# FLYBACK_220-24V.net
KiCad netlist of a schematic drawn in Altium Designer
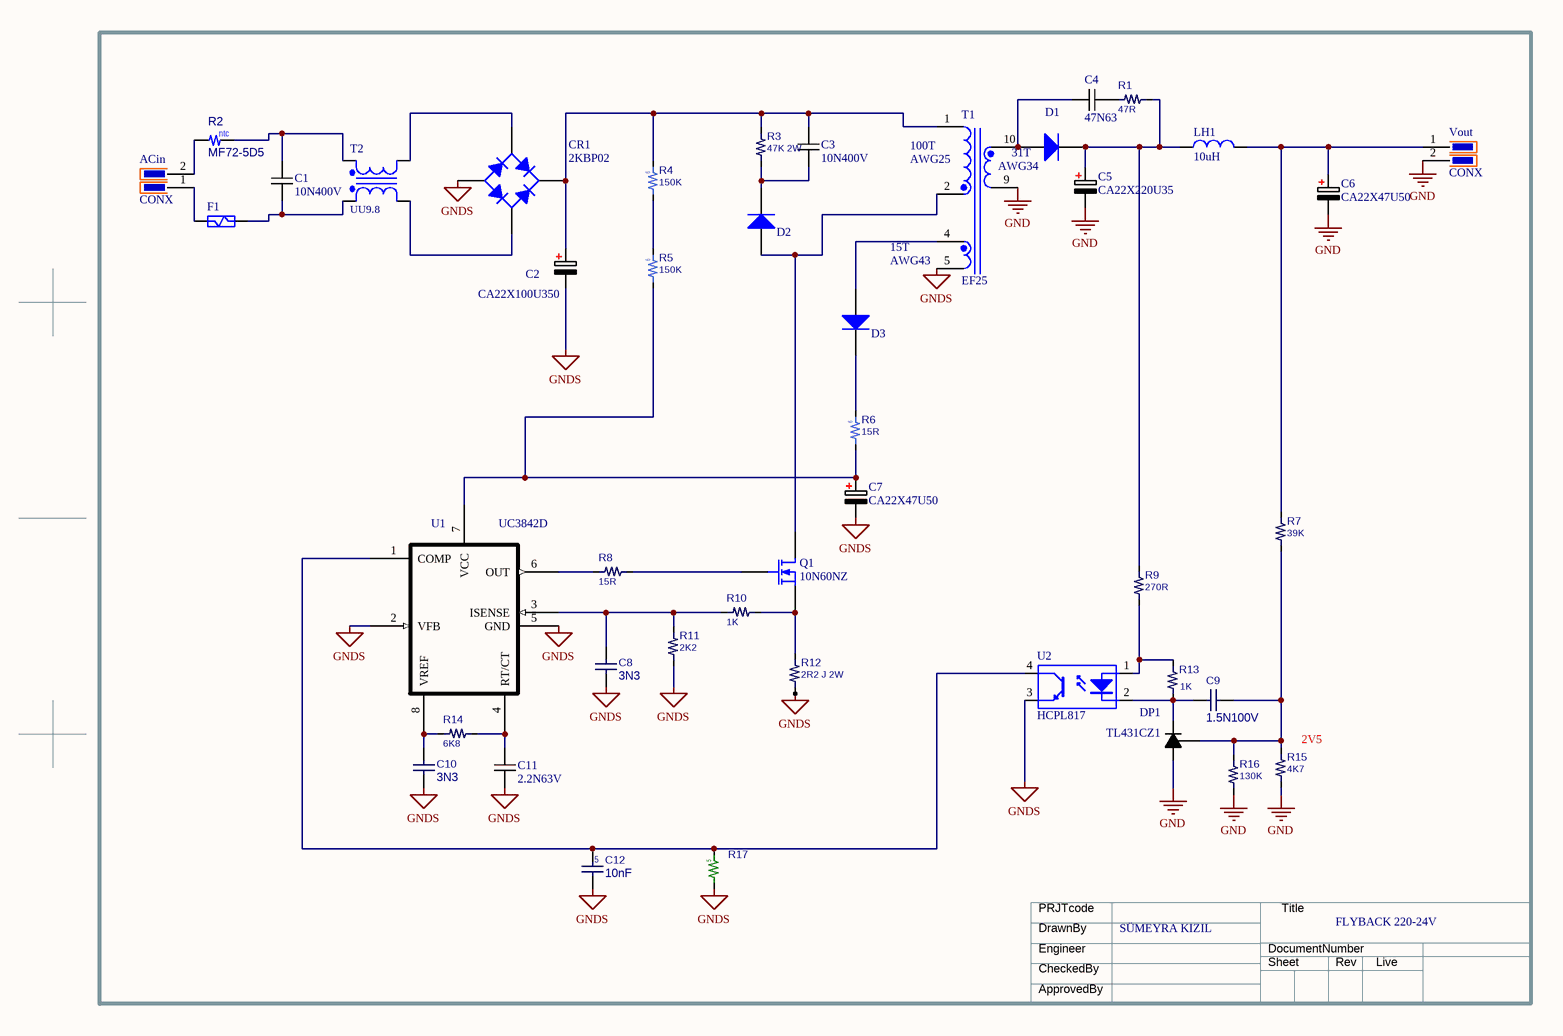
[diagram p0: FLYBACK 220-24V.SchDoc]

(export (version "E")
  (design (tool "Eeschema 10.0.6"))
  (components
    (comp (ref "ACin")
      (value "CONX")
      (footprint "MBDK122")
      (description "X PIN CONN")
      (libsource (lib "") (part "CON2X_1"))
    )
    (comp (ref "C1")
      (value "10N400V")
      (footprint "RAD0.3")
      (description "METALLISED POLYSTER CAP")
      (fields
        (field (name "MANUFACTURER") "Generic Components")
        (field (name "Comment") "CM03Y10N0V400")
        (field (name "PUBLISHER") "NET")
      )
      (libsource (lib "CM") (part "CM03Y10N0V400"))
    )
    (comp (ref "C2")
      (value "CA22X100U350")
      (footprint "24X30")
      (description "Electrolytic Capacitor general use")
      (fields (field (name "MANUFACTURER") "Generic Components"))
      (libsource (lib "CA22") (part "CA22X68U350"))
    )
    (comp (ref "C3")
      (value "10N400V")
      (footprint "RAD0.2")
      (description "METALLISED POLYSTER CAP")
      (fields
        (field (name "MANUFACTURER") "Generic Components")
        (field (name "Comment") "CM02Y10N0V400")
        (field (name "PUBLISHER") "NET")
      )
      (libsource (lib "CM") (part "CM02Y10N0V400"))
    )
    (comp (ref "C4")
      (value "47N63")
      (footprint "RAD0.2")
      (description "METALLISED POLYSTER CAP")
      (fields
        (field (name "MANUFACTURER") "Generic Components")
        (field (name "Comment") "CM02Y47N0V63")
        (field (name "PUBLISHER") "NET")
      )
      (libsource (lib "CM") (part "CM02Y47N0V63"))
    )
    (comp (ref "C5")
      (value "CA22X220U35")
      (footprint "8X12XP150")
      (description "Electrolytic Capacitor general use")
      (fields (field (name "MANUFACTURER") "Generic Components"))
      (libsource (lib "CA22") (part "CA22X220U35"))
    )
    (comp (ref "C6")
      (value "CA22X47U50")
      (footprint "8X12XP150")
      (description "Electrolytic Capacitor general use")
      (fields (field (name "MANUFACTURER") "Generic Components"))
      (libsource (lib "CA22") (part "CA22X47U50"))
    )
    (comp (ref "C7")
      (value "CA22X47U50")
      (footprint "6.3X11")
      (description "Electrolytic Capacitor general use")
      (fields (field (name "MANUFACTURER") "Generic Components"))
      (libsource (lib "CA22") (part "CA22X47U50"))
    )
    (comp (ref "C8")
      (value "3N3")
      (footprint "RAD0.2")
      (description "CERAMIC DISC CAPACITOR")
      (fields
        (field (name "MANUFACTURER") "Generic Components")
        (field (name "Comment") "CB02X3N30")
        (field (name "PUBLISHER") "Nettas Technology Center")
      )
      (libsource (lib "Sumeyra_1") (part "CB02X3N30"))
    )
    (comp (ref "C9")
      (value "1.5N100V")
      (footprint "RAD0.2")
      (description "CERAMIC DISC CAPACITOR")
      (fields
        (field (name "MANUFACTURER") "Generic Components")
        (field (name "Comment") "CB02X1N50")
        (field (name "PUBLISHER") "Nettas Technology Center")
      )
      (libsource (lib "CM") (part "CB02X1N50"))
    )
    (comp (ref "C10")
      (value "3N3")
      (footprint "RAD0.2")
      (description "CERAMIC DISC CAPACITOR")
      (fields
        (field (name "MANUFACTURER") "Generic Components")
        (field (name "Comment") "CB02X3N30")
        (field (name "PUBLISHER") "Nettas Technology Center")
      )
      (libsource (lib "Sumeyra_1") (part "CB02X3N30"))
    )
    (comp (ref "C11")
      (value "2.2N63V")
      (footprint "RAD0.2")
      (description "METALLISED POLYSTER CAP")
      (fields
        (field (name "MANUFACTURER") "Generic Components")
        (field (name "Comment") "CM02Y2N20V63")
        (field (name "PUBLISHER") "NET")
      )
      (libsource (lib "CM") (part "CM02Y2N20V63"))
    )
    (comp (ref "C12")
      (value "10nF")
      (footprint "RAD0.3")
      (description "TH Capacitor")
      (fields
        (field (name "MANUFACTURER") "Generic Components")
        (field (name "Comment") "CHC0805-10N0")
        (field (name "PUBLISHER") "Nettas Technology Center")
      )
      (libsource (lib "CHC") (part "CHC0805-10N0"))
    )
    (comp (ref "CR1")
      (value "2KBP02")
      (footprint "KBU")
      (description "2 Amp Single Phase Rectifier Bridge")
      (fields
        (field (name "MANUFACTURER") "International Rectifier")
        (field (name "PUBLISHER") "Altium Hobart Technology Centre")
      )
      (libsource (lib "Sumeyra_1") (part "2KBP02"))
    )
    (comp (ref "D1")
      (value "UF5402")
      (footprint "DO-41")
      (description "General Purpose ULTRA FAST Rectifiers")
      (fields
        (field (name "MANUFACTURER") "Generic Components")
        (field (name "PUBLISHER") "Altium Hobart Technology Centre")
      )
      (libsource (lib "DIODE") (part "UF5402"))
    )
    (comp (ref "D2")
      (value "UF4007")
      (footprint "DO-41")
      (description "General Purpose ULTRA FAST Rectifiers")
      (fields
        (field (name "MANUFACTURER") "Generic Components")
        (field (name "PUBLISHER") "Altium Hobart Technology Centre")
      )
      (libsource (lib "DIODE") (part "UF4007"))
    )
    (comp (ref "D3")
      (value "UF4007")
      (footprint "DO-41")
      (description "General Purpose ULTRA FAST Rectifiers")
      (fields
        (field (name "MANUFACTURER") "Generic Components")
        (field (name "PUBLISHER") "Altium Hobart Technology Centre")
      )
      (libsource (lib "DIODE") (part "UF4007"))
    )
    (comp (ref "DP1")
      (value "TL431CZ1")
      (footprint "TL431")
      (description "Programmable Voltage Reference")
      (fields
        (field (name "MANUFACTURER") "ST-Microelectronics")
        (field (name "PUBLISHER") "Altium Hobart Technology Centre")
      )
      (libsource (lib "INTEGRATED") (part "TL431CZ1"))
    )
    (comp (ref "F1")
      (value "~")
      (footprint "Sigorta Tutucu")
      (description "Fuse")
      (fields
        (field (name "MANUFACTURER") "Generic Components")
        (field (name "PUBLISHER") "Altium Hobart Technology Centre")
      )
      (libsource (lib "Sumeyra_1") (part "FUSE-GL600"))
    )
    (comp (ref "LH1")
      (value "10uH")
      (footprint "10X13L")
      (description "LH 10uH")
      (fields
        (field (name "MANUFACTURER") "Generic Components")
        (field (name "PUBLISHER") "Altium Hobart Technology Centre")
      )
      (libsource (lib "MAGNETIC") (part "Inductor"))
    )
    (comp (ref "Q1")
      (value "10N60NZ")
      (footprint "TO220")
      (description "FULLY AUTOPROTECTED POWER MOSFET")
      (fields
        (field (name "MANUFACTURER") "Generic Components")
        (field (name "PUBLISHER") "Altium Hobart Technology Centre")
      )
      (libsource (lib "Sumeyra_1") (part "10N60NZ"))
    )
    (comp (ref "R1")
      (value "47R")
      (footprint "AXIAL0.4")
      (description "AXIAL Resistor 0.4")
      (fields
        (field (name "MANUFACTURER") "Generic Components")
        (field (name "Comment") "RF24-47R0")
        (field (name "PUBLISHER") "Nettas Technology Center")
      )
      (libsource (lib "RF24") (part "RF24-47R0"))
    )
    (comp (ref "R2")
      (value "MF72-5D5")
      (footprint "RAD0.3NTC")
      (description "Power NTC Thermistor")
      (fields
        (field (name "MANUFACTURER") "Generic Components")
        (field (name "PUBLISHER") "Nettas Technology Center")
      )
      (libsource (lib "RF24") (part "MF72-5D5"))
    )
    (comp (ref "R3")
      (value "47K 2W")
      (footprint "AXIAL0.7")
      (description "AXIAL Resistor 0.7")
      (fields
        (field (name "MANUFACTURER") "Generic Components")
        (field (name "Comment") "RF13-47K0")
        (field (name "PUBLISHER") "Nettas Technology Center")
      )
      (libsource (lib "Sumeyra_1") (part "RF13-47K0"))
    )
    (comp (ref "R4")
      (value "150K")
      (footprint "AXIAL0.4")
      (description "SMD Resistor")
      (fields
        (field (name "MANUFACTURER") "Generic Components")
        (field (name "Comment") "CHR1206-15R0")
        (field (name "PUBLISHER") "Nettas Technology Center")
      )
      (libsource (lib "CHR") (part "CHR1206-15R0"))
    )
    (comp (ref "R5")
      (value "150K")
      (footprint "AXIAL0.4")
      (description "SMD Resistor")
      (fields
        (field (name "MANUFACTURER") "Generic Components")
        (field (name "Comment") "CHR1206-15R0")
        (field (name "PUBLISHER") "Nettas Technology Center")
      )
      (libsource (lib "CHR") (part "CHR1206-15R0"))
    )
    (comp (ref "R6")
      (value "15R")
      (footprint "AXIAL0.5")
      (description "SMD Resistor")
      (fields
        (field (name "MANUFACTURER") "Generic Components")
        (field (name "Comment") "CHR1206-15R0")
        (field (name "PUBLISHER") "Nettas Technology Center")
      )
      (libsource (lib "CHR") (part "CHR1206-15R0"))
    )
    (comp (ref "R7")
      (value "39K")
      (footprint "AXIAL0.5")
      (description "AXIAL Resistor")
      (fields
        (field (name "MANUFACTURER") "Generic Components")
        (field (name "Comment") "RF24-39K0")
        (field (name "PUBLISHER") "Nettas Technology Center")
      )
      (libsource (lib "RF24") (part "RF24-39K0"))
    )
    (comp (ref "R8")
      (value "15R")
      (footprint "AXIAL0.4")
      (description "AXIAL Resistor")
      (fields
        (field (name "MANUFACTURER") "Generic Components")
        (field (name "Comment") "RF24-15R0")
        (field (name "PUBLISHER") "Nettas Technology Center")
      )
      (libsource (lib "RF24") (part "RF24-15R0"))
    )
    (comp (ref "R9")
      (value "270R")
      (footprint "AXIAL0.6")
      (description "AXIAL Resistor")
      (fields
        (field (name "MANUFACTURER") "Generic Components")
        (field (name "Comment") "RF24-270R")
        (field (name "PUBLISHER") "Nettas Technology Center")
      )
      (libsource (lib "RF24") (part "RF24-270R"))
    )
    (comp (ref "R10")
      (value "1K")
      (footprint "AXIAL0.4")
      (description "AXIAL Resistor")
      (fields
        (field (name "MANUFACTURER") "Generic Components")
        (field (name "Comment") "RF24-1K00")
        (field (name "PUBLISHER") "Nettas Technology Center")
      )
      (libsource (lib "RF24") (part "RF24-1K00"))
    )
    (comp (ref "R11")
      (value "2K2")
      (footprint "AXIAL0.4")
      (description "AXIAL Resistor")
      (fields
        (field (name "MANUFACTURER") "Generic Components")
        (field (name "Comment") "RF24-2K20")
        (field (name "PUBLISHER") "Nettas Technology Center")
      )
      (libsource (lib "RF24") (part "RF24-2K20"))
    )
    (comp (ref "R12")
      (value "2R2 J 2W")
      (footprint "AXIAL0.7")
      (description "AXIAL WIRE Resistor")
      (fields
        (field (name "MANUFACTURER") "Generic Components")
        (field (name "Comment") "RW02J-2R20")
        (field (name "PUBLISHER") "Nettas Technology Center")
      )
      (libsource (lib "RF24") (part "RW02J-2R20"))
    )
    (comp (ref "R13")
      (value "1K")
      (footprint "AXIAL0.4")
      (description "AXIAL Resistor")
      (fields
        (field (name "MANUFACTURER") "Generic Components")
        (field (name "Comment") "RF24-1K00")
        (field (name "PUBLISHER") "Nettas Technology Center")
      )
      (libsource (lib "RF24") (part "RF24-1K00"))
    )
    (comp (ref "R14")
      (value "6K8")
      (footprint "AXIAL0.4")
      (description "AXIAL Resistor")
      (fields
        (field (name "MANUFACTURER") "Generic Components")
        (field (name "Comment") "RF24-6K80")
        (field (name "PUBLISHER") "Nettas Technology Center")
      )
      (libsource (lib "RF24") (part "RF24-6K80"))
    )
    (comp (ref "R15")
      (value "4K7")
      (footprint "AXIAL0.4")
      (description "AXIAL Resistor")
      (fields
        (field (name "MANUFACTURER") "Generic Components")
        (field (name "Comment") "RF24-4K70")
        (field (name "PUBLISHER") "Nettas Technology Center")
      )
      (libsource (lib "RF24") (part "RF24-4K70"))
    )
    (comp (ref "R16")
      (value "130K")
      (footprint "AXIAL0.4")
      (description "AXIAL Resistor")
      (fields
        (field (name "MANUFACTURER") "Generic Components")
        (field (name "Comment") "RF24-130K")
        (field (name "PUBLISHER") "Nettas Technology Center")
      )
      (libsource (lib "RF24") (part "RF24-130K"))
    )
    (comp (ref "R17")
      (value "CHR0805-10K0")
      (footprint "AXIAL0.4")
      (description "TH Resistor")
      (fields
        (field (name "MANUFACTURER") "Generic Components")
        (field (name "PUBLISHER") "Nettas Technology Center")
      )
      (libsource (lib "CHR") (part "CHR0805-10K0"))
    )
    (comp (ref "T1")
      (value "EF25")
      (footprint "TRF_EF25_40")
      (description "TRF_EF25_40")
      (fields
        (field (name "MANUFACTURER") "Generic Components")
        (field (name "PUBLISHER") "Altium Hobart Technology Centre")
      )
      (libsource (lib "Sumeyra_1") (part "TRF_EF25_40"))
    )
    (comp (ref "T2")
      (value "UU9.8")
      (footprint "LFILT11")
      (description "LINEFILTER CUPL TRF")
      (libsource (lib "Sumeyra_1") (part "LINEFILTER12"))
    )
    (comp (ref "U1")
      (value "UC3842D")
      (footprint "DIP8")
      (description "SMPS Controller")
      (libsource (lib "INTEGRATED") (part "UC3844D1"))
    )
    (comp (ref "U2")
      (value "HCPL817")
      (footprint "DIP4")
      (description "High Density Mounting Type Photocoupler")
      (fields (field (name "MANUFACTURER") "www.cosmo-ic.com"))
      (libsource (lib "OPTO") (part "HCPL817"))
    )
    (comp (ref "Vout")
      (value "CONX")
      (footprint "MBDK122")
      (description "X PIN CONN")
      (libsource (lib "Sumeyra") (part "CON2X"))
    )
  )
  (nets
    (net (code "1") (name "GND") (class "Default")
      (node (ref "C5") (pin "2") (pinfunction "2_2") (pintype "passive"))
      (node (ref "C6") (pin "2") (pinfunction "2_2") (pintype "passive"))
      (node (ref "DP1") (pin "2") (pinfunction "A_2") (pintype "passive"))
      (node (ref "R15") (pin "1") (pinfunction "1_1") (pintype "passive"))
      (node (ref "R16") (pin "1") (pinfunction "1_1") (pintype "passive"))
      (node (ref "T1") (pin "9") (pinfunction "Sec-_9") (pintype "passive"))
      (node (ref "Vout") (pin "2") (pintype "passive"))
    )
    (net (code "2") (name "GNDS") (class "Default")
      (node (ref "C10") (pin "1") (pinfunction "1_1") (pintype "passive"))
      (node (ref "C11") (pin "1") (pinfunction "1_1") (pintype "passive"))
      (node (ref "C12") (pin "1") (pinfunction "1_1") (pintype "passive"))
      (node (ref "C2") (pin "2") (pinfunction "2_2") (pintype "passive"))
      (node (ref "C7") (pin "2") (pinfunction "2_2") (pintype "passive"))
      (node (ref "C8") (pin "1") (pinfunction "1_1") (pintype "passive"))
      (node (ref "CR1") (pin "4") (pinfunction "A_4") (pintype "passive"))
      (node (ref "R11") (pin "1") (pinfunction "1_1") (pintype "passive"))
      (node (ref "R12") (pin "1") (pinfunction "1_1") (pintype "passive"))
      (node (ref "R17") (pin "1") (pinfunction "1_1") (pintype "passive"))
      (node (ref "T1") (pin "5") (pinfunction "FB-_5") (pintype "passive"))
      (node (ref "U1") (pin "2") (pinfunction "VFB_2") (pintype "input"))
      (node (ref "U1") (pin "5") (pinfunction "GND_5") (pintype "power_in"))
      (node (ref "U2") (pin "3") (pinfunction "E_3") (pintype "passive"))
    )
    (net (code "3") (name "Net-(ACin-Pad1)") (class "Default")
      (node (ref "ACin") (pin "1") (pintype "passive"))
      (node (ref "F1") (pin "1") (pinfunction "1_1") (pintype "passive"))
    )
    (net (code "4") (name "Net-(ACin-Pad2)") (class "Default")
      (node (ref "ACin") (pin "2") (pintype "passive"))
      (node (ref "R2") (pin "1") (pinfunction "1_1") (pintype "passive"))
    )
    (net (code "5") (name "Net-(C1-Pad1)") (class "Default")
      (node (ref "C1") (pin "1") (pinfunction "1_1") (pintype "passive"))
      (node (ref "F1") (pin "2") (pinfunction "2_2") (pintype "passive"))
      (node (ref "T2") (pin "1") (pinfunction "1_1") (pintype "passive"))
    )
    (net (code "6") (name "Net-(C1-Pad2)") (class "Default")
      (node (ref "C1") (pin "2") (pinfunction "2_2") (pintype "passive"))
      (node (ref "R2") (pin "2") (pinfunction "2_2") (pintype "passive"))
      (node (ref "T2") (pin "2") (pinfunction "2_2") (pintype "passive"))
    )
    (net (code "7") (name "Net-(C4-Pad2)") (class "Default")
      (node (ref "C4") (pin "2") (pinfunction "2_2") (pintype "passive"))
      (node (ref "R1") (pin "1") (pinfunction "1_1") (pintype "passive"))
    )
    (net (code "8") (name "Net-(C6-Pad1)") (class "Default")
      (node (ref "C6") (pin "1") (pinfunction "1_1") (pintype "passive"))
      (node (ref "LH1") (pin "2") (pinfunction "2_2") (pintype "passive"))
      (node (ref "R7") (pin "2") (pinfunction "2_2") (pintype "passive"))
      (node (ref "Vout") (pin "1") (pintype "passive"))
    )
    (net (code "9") (name "Net-(CR1-C-Pad2)") (class "Default")
      (node (ref "CR1") (pin "2") (pinfunction "C_2") (pintype "passive"))
      (node (ref "T2") (pin "4") (pinfunction "4_4") (pintype "passive"))
    )
    (net (code "10") (name "Net-(CR1-C-Pad3)") (class "Default")
      (node (ref "CR1") (pin "3") (pinfunction "C_3") (pintype "passive"))
      (node (ref "T2") (pin "3") (pinfunction "3_3") (pintype "passive"))
    )
    (net (code "11") (name "Net-(CR1-K)") (class "Default")
      (node (ref "C2") (pin "1") (pinfunction "1_1") (pintype "passive"))
      (node (ref "C3") (pin "2") (pinfunction "2_2") (pintype "passive"))
      (node (ref "CR1") (pin "1") (pinfunction "K_1") (pintype "passive"))
      (node (ref "R3") (pin "2") (pinfunction "2_2") (pintype "passive"))
      (node (ref "R4") (pin "2") (pinfunction "2_2") (pintype "passive"))
      (node (ref "T1") (pin "1") (pinfunction "Pri+_1") (pintype "passive"))
    )
    (net (code "12") (name "Net-(D1-A)") (class "Default")
      (node (ref "C4") (pin "1") (pinfunction "1_1") (pintype "passive"))
      (node (ref "D1") (pin "1") (pinfunction "A_1") (pintype "passive"))
      (node (ref "T1") (pin "10") (pinfunction "Sec+_10") (pintype "passive"))
    )
    (net (code "13") (name "Net-(D1-K)") (class "Default")
      (node (ref "C5") (pin "1") (pinfunction "1_1") (pintype "passive"))
      (node (ref "D1") (pin "2") (pinfunction "K_2") (pintype "passive"))
      (node (ref "LH1") (pin "1") (pinfunction "1_1") (pintype "passive"))
      (node (ref "R1") (pin "2") (pinfunction "2_2") (pintype "passive"))
      (node (ref "R9") (pin "2") (pinfunction "2_2") (pintype "passive"))
    )
    (net (code "14") (name "Net-(D2-A)") (class "Default")
      (node (ref "D2") (pin "1") (pinfunction "A_1") (pintype "passive"))
      (node (ref "Q1") (pin "2") (pinfunction "D_2") (pintype "passive"))
      (node (ref "T1") (pin "2") (pinfunction "Pri-_2") (pintype "passive"))
    )
    (net (code "15") (name "Net-(D2-K)") (class "Default")
      (node (ref "C3") (pin "1") (pinfunction "1_1") (pintype "passive"))
      (node (ref "D2") (pin "2") (pinfunction "K_2") (pintype "passive"))
      (node (ref "R3") (pin "1") (pinfunction "1_1") (pintype "passive"))
    )
    (net (code "16") (name "Net-(D3-A)") (class "Default")
      (node (ref "D3") (pin "1") (pinfunction "A_1") (pintype "passive"))
      (node (ref "T1") (pin "4") (pinfunction "FB+_4") (pintype "passive"))
    )
    (net (code "17") (name "Net-(D3-K)") (class "Default")
      (node (ref "D3") (pin "2") (pinfunction "K_2") (pintype "passive"))
      (node (ref "R6") (pin "2") (pinfunction "2_2") (pintype "passive"))
    )
    (net (code "18") (name "Net-(DP1-K)") (class "Default")
      (node (ref "C9") (pin "1") (pinfunction "1_1") (pintype "passive"))
      (node (ref "DP1") (pin "1") (pinfunction "K_1") (pintype "passive"))
      (node (ref "R13") (pin "1") (pinfunction "1_1") (pintype "passive"))
      (node (ref "U2") (pin "2") (pinfunction "K_2") (pintype "passive"))
    )
    (net (code "19") (name "Net-(DP1-REF)") (class "Default")
      (node (ref "C9") (pin "2") (pinfunction "2_2") (pintype "passive"))
      (node (ref "DP1") (pin "3") (pinfunction "REF_3") (pintype "passive"))
      (node (ref "R15") (pin "2") (pinfunction "2_2") (pintype "passive"))
      (node (ref "R16") (pin "2") (pinfunction "2_2") (pintype "passive"))
      (node (ref "R7") (pin "1") (pinfunction "1_1") (pintype "passive"))
    )
    (net (code "20") (name "Net-(Q1-G)") (class "Default")
      (node (ref "Q1") (pin "1") (pinfunction "G_1") (pintype "passive"))
      (node (ref "R8") (pin "2") (pinfunction "2_2") (pintype "passive"))
    )
    (net (code "21") (name "Net-(Q1-S)") (class "Default")
      (node (ref "Q1") (pin "3") (pinfunction "S_3") (pintype "passive"))
      (node (ref "R10") (pin "2") (pinfunction "2_2") (pintype "passive"))
      (node (ref "R12") (pin "2") (pinfunction "2_2") (pintype "passive"))
    )
    (net (code "22") (name "Net-(R4-Pad1)") (class "Default")
      (node (ref "R4") (pin "1") (pinfunction "1_1") (pintype "passive"))
      (node (ref "R5") (pin "2") (pinfunction "2_2") (pintype "passive"))
    )
    (net (code "23") (name "Net-(U1-COMP)") (class "Default")
      (node (ref "C12") (pin "2") (pinfunction "2_2") (pintype "passive"))
      (node (ref "R17") (pin "2") (pinfunction "2_2") (pintype "passive"))
      (node (ref "U1") (pin "1") (pinfunction "COMP_1") (pintype "passive"))
      (node (ref "U2") (pin "4") (pinfunction "C_4") (pintype "passive"))
    )
    (net (code "24") (name "Net-(U1-ISENSE)") (class "Default")
      (node (ref "C8") (pin "2") (pinfunction "2_2") (pintype "passive"))
      (node (ref "R10") (pin "1") (pinfunction "1_1") (pintype "passive"))
      (node (ref "R11") (pin "2") (pinfunction "2_2") (pintype "passive"))
      (node (ref "U1") (pin "3") (pinfunction "ISENSE_3") (pintype "input"))
    )
    (net (code "25") (name "Net-(U1-OUT)") (class "Default")
      (node (ref "R8") (pin "1") (pinfunction "1_1") (pintype "passive"))
      (node (ref "U1") (pin "6") (pinfunction "OUT_6") (pintype "output"))
    )
    (net (code "26") (name "Net-(U1-RT{slash}CT)") (class "Default")
      (node (ref "C11") (pin "2") (pinfunction "2_2") (pintype "passive"))
      (node (ref "R14") (pin "2") (pinfunction "2_2") (pintype "passive"))
      (node (ref "U1") (pin "4") (pinfunction "RT/CT_4") (pintype "passive"))
    )
    (net (code "27") (name "Net-(U1-VCC)") (class "Default")
      (node (ref "C7") (pin "1") (pinfunction "1_1") (pintype "passive"))
      (node (ref "R5") (pin "1") (pinfunction "1_1") (pintype "passive"))
      (node (ref "R6") (pin "1") (pinfunction "1_1") (pintype "passive"))
      (node (ref "U1") (pin "7") (pinfunction "VCC_7") (pintype "power_in"))
    )
    (net (code "28") (name "Net-(U1-VREF)") (class "Default")
      (node (ref "C10") (pin "2") (pinfunction "2_2") (pintype "passive"))
      (node (ref "R14") (pin "1") (pinfunction "1_1") (pintype "passive"))
      (node (ref "U1") (pin "8") (pinfunction "VREF_8") (pintype "passive"))
    )
    (net (code "29") (name "Net-(U2-A)") (class "Default")
      (node (ref "R13") (pin "2") (pinfunction "2_2") (pintype "passive"))
      (node (ref "R9") (pin "1") (pinfunction "1_1") (pintype "passive"))
      (node (ref "U2") (pin "1") (pinfunction "A_1") (pintype "passive"))
    )
  )
)
